# Connectors.net
KiCad netlist of a schematic drawn in Altium Designer
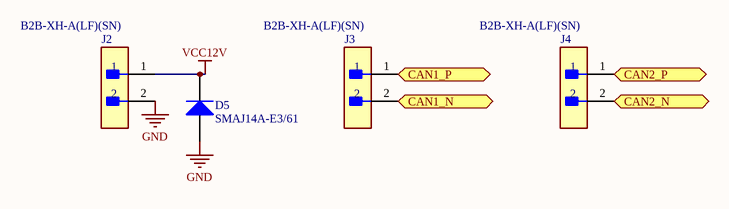
[diagram p0: Connectors.SchDoc]

(export (version "E")
  (design (tool "Eeschema 10.0.6"))
  (components
    (comp (ref "D5")
      (value "SMAJ14A-E3/61")
      (footprint "VISH-DO-214AC-2_L")
      (fields (field (name "MANUFACTURER") "Vishay Semiconductor"))
      (libsource (lib "Altium Content Vault") (part "VISH-K1A2-2"))
    )
    (comp (ref "J2")
      (value "B2B-XH-A(LF)(SN)")
      (footprint "FP-B2B-XH-A_LF_SN-MFG")
      (description "CONN HEADER VERT 2POS 2.5MM")
      (libsource (lib "Altium Content Vault") (part "3bc925449376181038e59eaffc5286c"))
    )
    (comp (ref "J3")
      (value "B2B-XH-A(LF)(SN)")
      (footprint "FP-B2B-XH-A_LF_SN-MFG")
      (description "CONN HEADER VERT 2POS 2.5MM")
      (libsource (lib "Altium Content Vault") (part "3bc925449376181038e59eaffc5286c"))
    )
    (comp (ref "J4")
      (value "B2B-XH-A(LF)(SN)")
      (footprint "FP-B2B-XH-A_LF_SN-MFG")
      (description "CONN HEADER VERT 2POS 2.5MM")
      (libsource (lib "Altium Content Vault") (part "3bc925449376181038e59eaffc5286c"))
    )
  )
  (nets
    (net (code "1") (name "/CAN1_N") (class "Default")
      (node (ref "J3") (pin "2") (pinfunction "2_2") (pintype "passive"))
    )
    (net (code "2") (name "/CAN1_P") (class "Default")
      (node (ref "J3") (pin "1") (pinfunction "1_1") (pintype "passive"))
    )
    (net (code "3") (name "/CAN2_N") (class "Default")
      (node (ref "J4") (pin "2") (pinfunction "2_2") (pintype "passive"))
    )
    (net (code "4") (name "/CAN2_P") (class "Default")
      (node (ref "J4") (pin "1") (pinfunction "1_1") (pintype "passive"))
    )
    (net (code "5") (name "GND") (class "Default")
      (node (ref "D5") (pin "2") (pinfunction "A_2") (pintype "passive"))
      (node (ref "J2") (pin "2") (pinfunction "2_2") (pintype "passive"))
    )
    (net (code "6") (name "VCC12V") (class "Default")
      (node (ref "D5") (pin "1") (pinfunction "K_1") (pintype "passive"))
      (node (ref "J2") (pin "1") (pinfunction "1_1") (pintype "passive"))
    )
  )
)
